# alarm.net
KiCad netlist of a schematic drawn in EasyEDA Pro
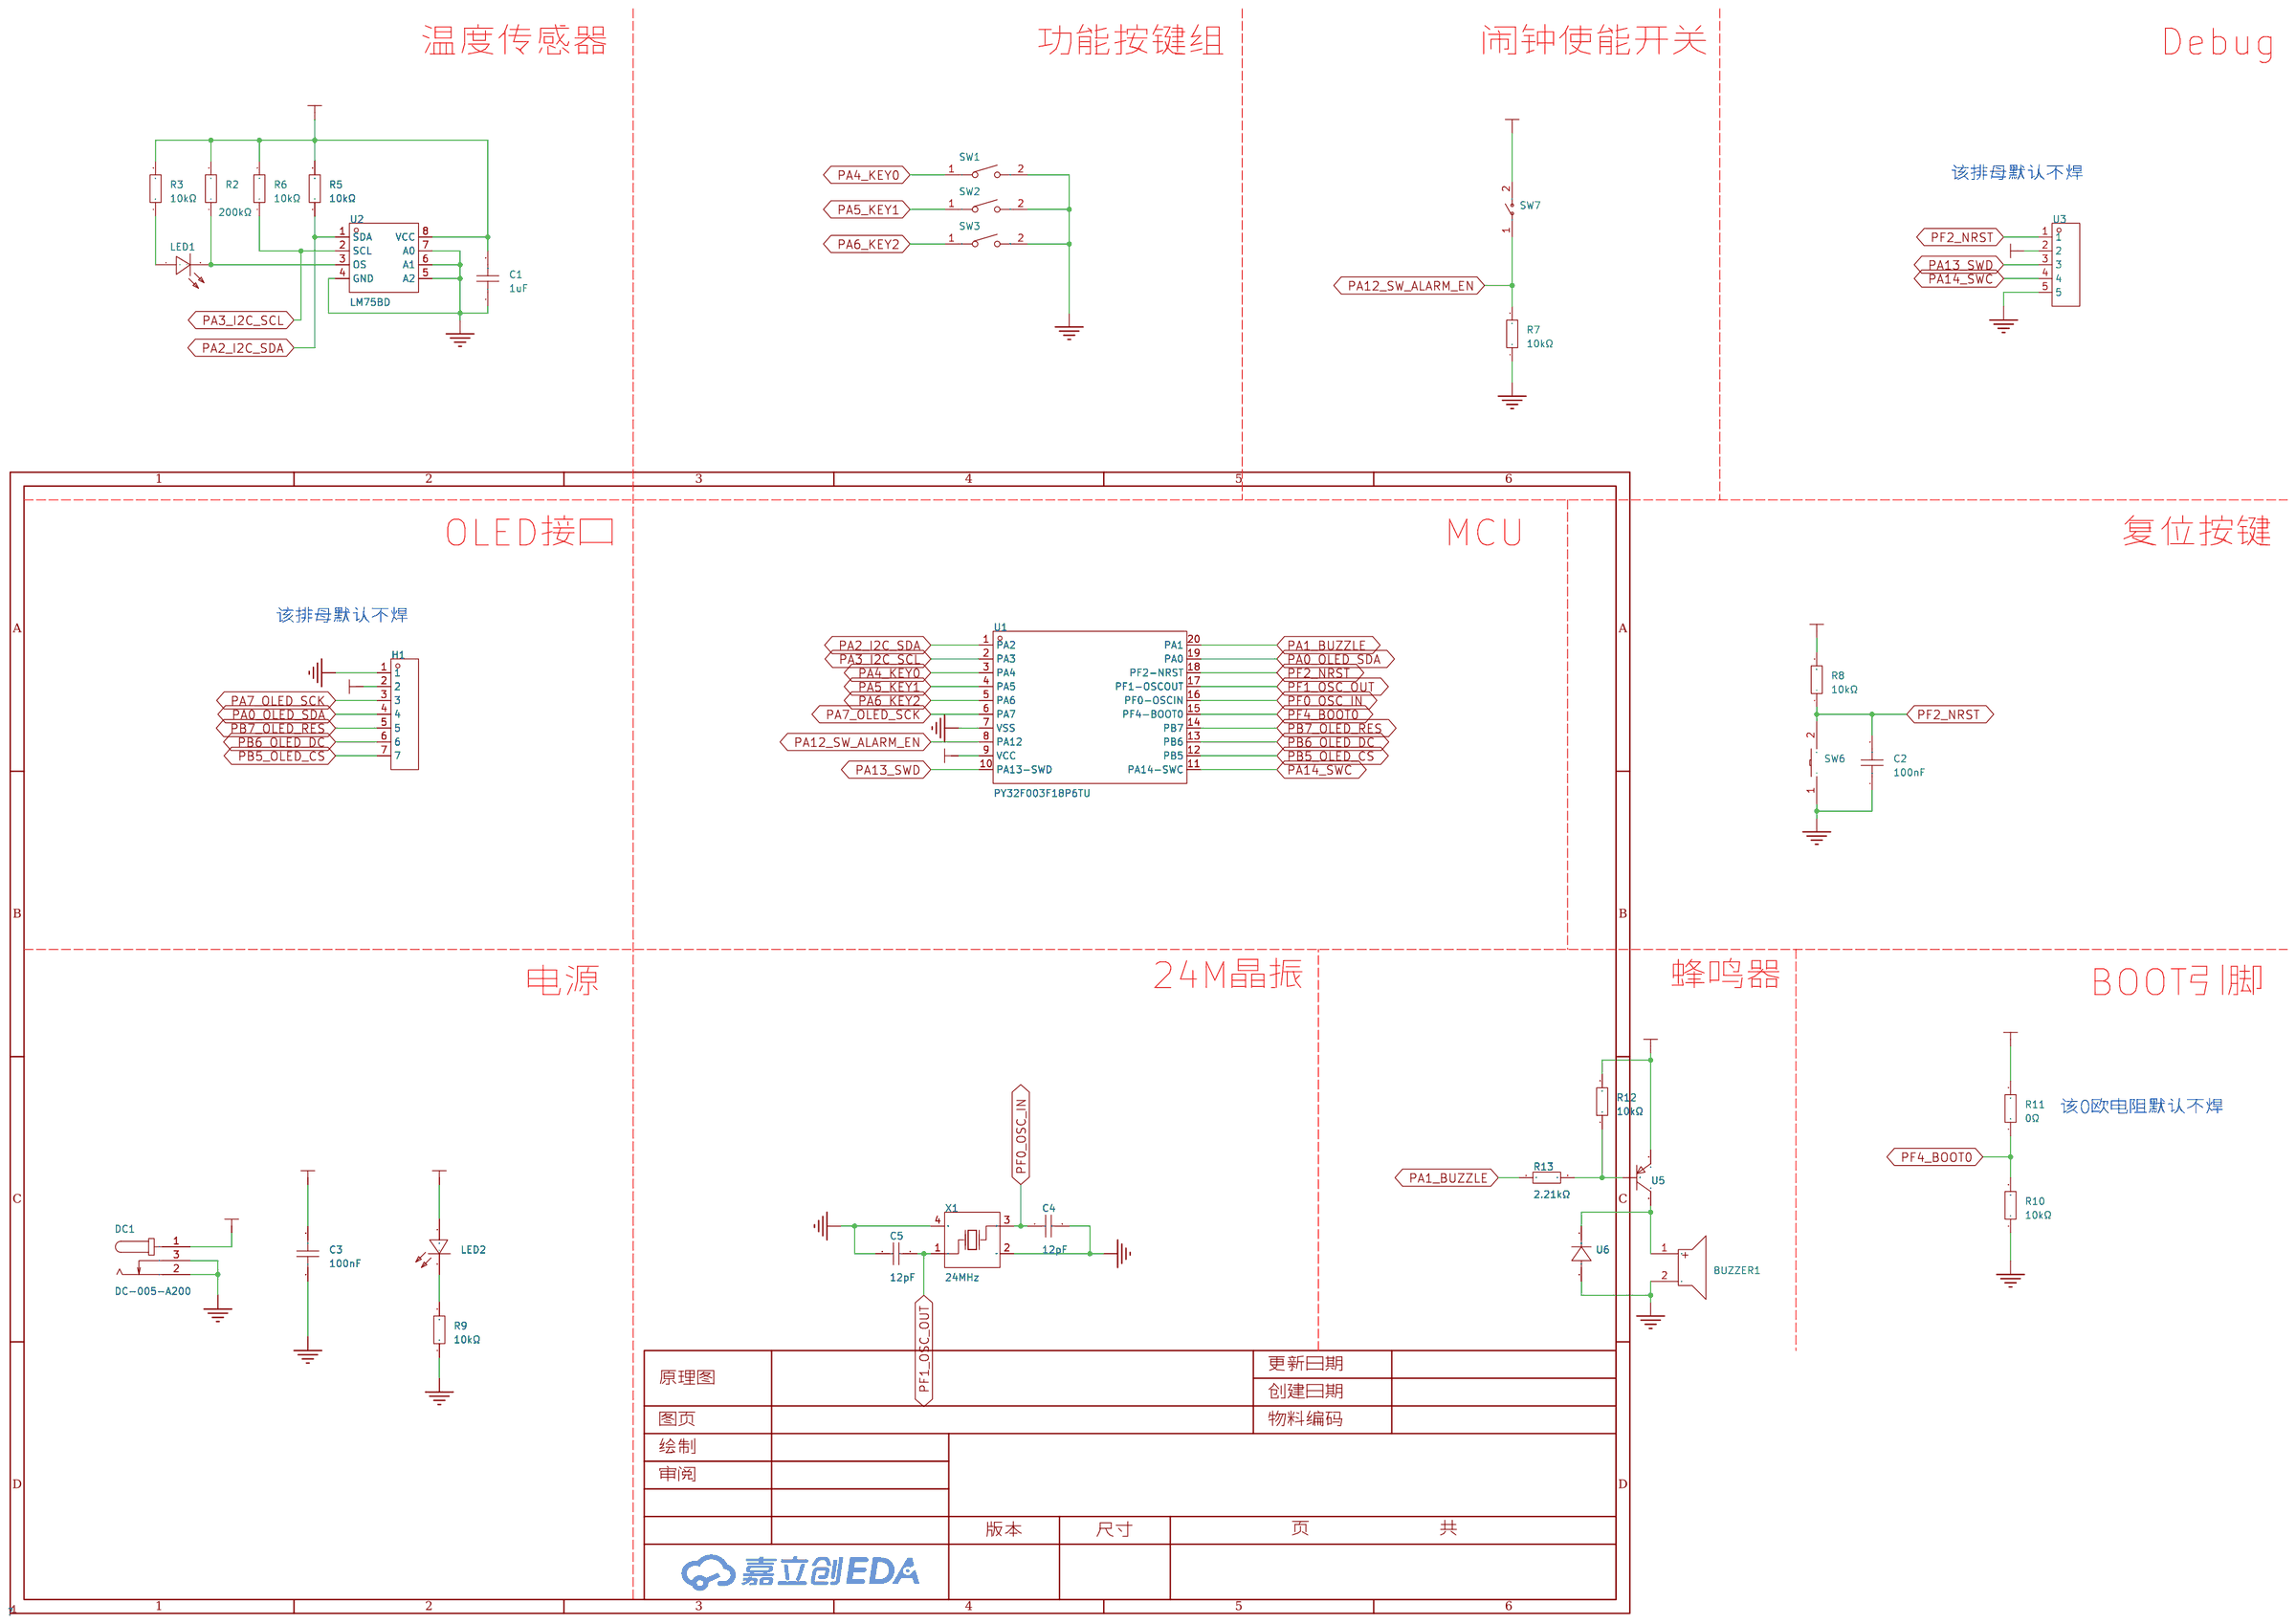
[diagram p0: schematic sheet]

(export (version "E")
  (design (tool "Eeschema 10.0.6"))
  (components
    (comp (ref "BUZZER1")
      (value "2.7kHz")
      (footprint "easyedapro:BUZ-TH_BD9.0-P4.00-D0.6-FD")
      (description "驱动方式:无源(外部驱动);构造类型:电磁式;频率:2.7kHz;声压(SPL):85dB@3V,10cm;")
      (fields (field (name "Manufacturer Part") "QMB-09B-03") (field (name "Manufacturer") "华能"))
      (libsource (lib "easyedapro") (part "QMB-09B-03"))
    )
    (comp (ref "C1")
      (value "1uF")
      (footprint "easyedapro:C0603")
      (description "容值:1uF;精度:±10%;额定电压:50V;材质(温度系数):X5R;")
      (fields
        (field (name "Manufacturer Part") "CL10A105KB8NNNC")
        (field (name "Manufacturer") "SAMSUNG(三星)")
      )
      (libsource (lib "easyedapro") (part "CL10A105KB8NNNC"))
    )
    (comp (ref "C2")
      (value "100nF")
      (footprint "easyedapro:C0603")
      (description "容值:100nF;精度:±10%;额定电压:50V;材质(温度系数):X7R;")
      (fields
        (field (name "Manufacturer Part") "CL10B104KB8NNNC")
        (field (name "Manufacturer") "SAMSUNG(三星)")
      )
      (libsource (lib "easyedapro") (part "CL10B104KB8NNNC"))
    )
    (comp (ref "C3")
      (value "100nF")
      (footprint "easyedapro:C0603")
      (description "容值:100nF;精度:±10%;额定电压:50V;材质(温度系数):X7R;")
      (fields
        (field (name "Manufacturer Part") "CL10B104KB8NNNC")
        (field (name "Manufacturer") "SAMSUNG(三星)")
      )
      (libsource (lib "easyedapro") (part "CL10B104KB8NNNC"))
    )
    (comp (ref "C4")
      (value "12pF")
      (footprint "easyedapro:C0603")
      (description "容值:12pF;精度:±5%;额定电压:50V;材质(温度系数):C0G;")
      (fields
        (field (name "Manufacturer Part") "CL10C120JB8NNNC")
        (field (name "Manufacturer") "SAMSUNG(三星)")
      )
      (libsource (lib "easyedapro") (part "CL10C120JB8NNNC"))
    )
    (comp (ref "C5")
      (value "12pF")
      (footprint "easyedapro:C0603")
      (description "容值:12pF;精度:±5%;额定电压:50V;材质(温度系数):C0G;")
      (fields
        (field (name "Manufacturer Part") "CL10C120JB8NNNC")
        (field (name "Manufacturer") "SAMSUNG(三星)")
      )
      (libsource (lib "easyedapro") (part "CL10C120JB8NNNC"))
    )
    (comp (ref "DC1")
      (value "DC-005-A200")
      (footprint "easyedapro:DC-IN-TH_DC-005-A200")
      (description "连接器类型:DC电源插座;安装方式:弯插;触点内径:2mm;触点外径:6.4mm;额定电流:3A;额定电压:30V;工作温度范围:-20°C~+70°C;")
      (fields (field (name "Manufacturer") "XUNPU(讯普)"))
      (libsource (lib "easyedapro") (part "DC-005-A200"))
    )
    (comp (ref "H1")
      (value "BX-PM2.54-1-7PY")
      (footprint "easyedapro:HDR-TH_7P-P2.54-V-F")
      (fields (field (name "Manufacturer") "Bossie(博锡)"))
      (libsource (lib "easyedapro") (part "BX-PM2.54-1-7PY"))
    )
    (comp (ref "LED1")
      (value "NCD0805R1")
      (footprint "easyedapro:LED0805-R-RD")
      (fields (field (name "Manufacturer") "国星光电"))
      (libsource (lib "easyedapro") (part "FC-2012HRK-620D"))
    )
    (comp (ref "LED2")
      (value "NCD0805R1")
      (footprint "easyedapro:LED0805-R-RD")
      (fields (field (name "Manufacturer") "国星光电"))
      (libsource (lib "easyedapro") (part "FC-2012HRK-620D"))
    )
    (comp (ref "R2")
      (value "200kΩ")
      (footprint "easyedapro:R0603")
      (description "电阻类型:厚膜电阻;阻值:200kΩ;精度:±1%;功率:100mW;最大工作电压:75V;温度系数:±100ppm/°C;")
      (fields
        (field (name "Manufacturer Part") "0603WAF2003T5E")
        (field (name "Manufacturer") "UNI-ROYAL(厚声)")
      )
      (libsource (lib "easyedapro") (part "0603WAF2003T5E"))
    )
    (comp (ref "R3")
      (value "10kΩ")
      (footprint "easyedapro:R0603")
      (description "电阻类型:厚膜电阻;阻值:10kΩ;精度:±1%;功率:100mW;最大工作电压:75V;温度系数:±100ppm/°C;")
      (fields
        (field (name "Manufacturer Part") "0603WAF1002T5E")
        (field (name "Manufacturer") "UNI-ROYAL(厚声)")
      )
      (libsource (lib "easyedapro") (part "0603WAF1002T5E"))
    )
    (comp (ref "R5")
      (value "10kΩ")
      (footprint "easyedapro:R0603")
      (description "电阻类型:厚膜电阻;阻值:10kΩ;精度:±1%;功率:100mW;最大工作电压:75V;温度系数:±100ppm/°C;")
      (fields
        (field (name "Manufacturer Part") "0603WAF1002T5E")
        (field (name "Manufacturer") "UNI-ROYAL(厚声)")
      )
      (libsource (lib "easyedapro") (part "0603WAF1002T5E"))
    )
    (comp (ref "R6")
      (value "10kΩ")
      (footprint "easyedapro:R0603")
      (description "电阻类型:厚膜电阻;阻值:10kΩ;精度:±1%;功率:100mW;最大工作电压:75V;温度系数:±100ppm/°C;")
      (fields
        (field (name "Manufacturer Part") "0603WAF1002T5E")
        (field (name "Manufacturer") "UNI-ROYAL(厚声)")
      )
      (libsource (lib "easyedapro") (part "0603WAF1002T5E"))
    )
    (comp (ref "R7")
      (value "10kΩ")
      (footprint "easyedapro:R0603")
      (description "电阻类型:厚膜电阻;阻值:10kΩ;精度:±1%;功率:100mW;最大工作电压:75V;温度系数:±100ppm/°C;")
      (fields
        (field (name "Manufacturer Part") "0603WAF1002T5E")
        (field (name "Manufacturer") "UNI-ROYAL(厚声)")
      )
      (libsource (lib "easyedapro") (part "0603WAF1002T5E"))
    )
    (comp (ref "R8")
      (value "10kΩ")
      (footprint "easyedapro:R0603")
      (description "电阻类型:厚膜电阻;阻值:10kΩ;精度:±1%;功率:100mW;最大工作电压:75V;温度系数:±100ppm/°C;")
      (fields
        (field (name "Manufacturer Part") "0603WAF1002T5E")
        (field (name "Manufacturer") "UNI-ROYAL(厚声)")
      )
      (libsource (lib "easyedapro") (part "0603WAF1002T5E"))
    )
    (comp (ref "R9")
      (value "10kΩ")
      (footprint "easyedapro:R0603")
      (description "电阻类型:厚膜电阻;阻值:10kΩ;精度:±1%;功率:100mW;最大工作电压:75V;温度系数:±100ppm/°C;")
      (fields
        (field (name "Manufacturer Part") "0603WAF1002T5E")
        (field (name "Manufacturer") "UNI-ROYAL(厚声)")
      )
      (libsource (lib "easyedapro") (part "0603WAF1002T5E"))
    )
    (comp (ref "R10")
      (value "10kΩ")
      (footprint "easyedapro:R0603")
      (description "电阻类型:厚膜电阻;阻值:10kΩ;精度:±1%;功率:100mW;最大工作电压:75V;温度系数:±100ppm/°C;")
      (fields
        (field (name "Manufacturer Part") "0603WAF1002T5E")
        (field (name "Manufacturer") "UNI-ROYAL(厚声)")
      )
      (libsource (lib "easyedapro") (part "0603WAF1002T5E"))
    )
    (comp (ref "R11")
      (value "0Ω")
      (footprint "easyedapro:R0805")
      (description "电阻类型:厚膜电阻;阻值:0Ω;精度:±1%;功率:125mW;最大工作电压:150V;温度系数:±800ppm/°C;")
      (fields
        (field (name "Manufacturer Part") "0805W8F0000T5E")
        (field (name "Manufacturer") "UNI-ROYAL(厚声)")
      )
      (libsource (lib "easyedapro") (part "0805W8F0000T5E"))
    )
    (comp (ref "R12")
      (value "10kΩ")
      (footprint "easyedapro:R0603")
      (description "电阻类型:厚膜电阻;阻值:10kΩ;精度:±1%;功率:100mW;最大工作电压:75V;温度系数:±100ppm/°C;")
      (fields
        (field (name "Manufacturer Part") "0603WAF1002T5E")
        (field (name "Manufacturer") "UNI-ROYAL(厚声)")
      )
      (libsource (lib "easyedapro") (part "0603WAF1002T5E"))
    )
    (comp (ref "R13")
      (value "2.21kΩ")
      (footprint "easyedapro:R0603")
      (description "电阻类型:厚膜电阻;阻值:2.21kΩ;精度:±1%;功率:100mW;最大工作电压:75V;温度系数:±100ppm/°C;")
      (fields
        (field (name "Manufacturer Part") "0603WAF2211T5E")
        (field (name "Manufacturer") "UNI-ROYAL(厚声)")
      )
      (libsource (lib "easyedapro") (part "0603WAF2211T5E"))
    )
    (comp (ref "SW1")
      (value "TS-1088-AR02016")
      (footprint "easyedapro:SW-SMD_L3.9-W3.0-P4.45")
      (fields (field (name "Manufacturer") "XUNPU(讯普)"))
      (libsource (lib "easyedapro") (part "TS-1088-AR02016"))
    )
    (comp (ref "SW2")
      (value "TS-1088-AR02016")
      (footprint "easyedapro:SW-SMD_L3.9-W3.0-P4.45")
      (fields (field (name "Manufacturer") "XUNPU(讯普)"))
      (libsource (lib "easyedapro") (part "TS-1088-AR02016"))
    )
    (comp (ref "SW3")
      (value "TS-1088-AR02016")
      (footprint "easyedapro:SW-SMD_L3.9-W3.0-P4.45")
      (fields (field (name "Manufacturer") "XUNPU(讯普)"))
      (libsource (lib "easyedapro") (part "TS-1088-AR02016"))
    )
    (comp (ref "SW6")
      (value "TS-1101-C-W")
      (footprint "easyedapro:SW-SMD_L6.0-W3.3-LS8.0")
      (fields (field (name "Manufacturer") "XKB Connectivity(中国星坤)"))
      (libsource (lib "easyedapro") (part "TS-1101-C-W"))
    )
    (comp (ref "SW7")
      (value "KCD11-2P-R")
      (footprint "easyedapro:SW-TH_2P-L15.0-W10.5-P5.00_KCD11-2P-R")
      (description "带灯:无;引脚样式:焊片;额定电流:3A;额定电压(AC):250V;额定电压(DC):-;电路结构:单刀单掷;机械寿命:1万次;")
      (fields (field (name "Manufacturer") "SHOU HAN(首韩)"))
      (libsource (lib "easyedapro") (part "KCD11-2P-R"))
    )
    (comp (ref "U1")
      (value "PY32F003F18P6TU")
      (footprint "easyedapro:TSSOP-20_L6.5-W4.4-P0.65-LS6.4-BL")
      (fields (field (name "Manufacturer") "PUYA(普冉)"))
      (libsource (lib "easyedapro") (part "PY32F003F18P6TU"))
    )
    (comp (ref "U2")
      (value "LM75BD")
      (footprint "easyedapro:SOIC-8_L4.9-W3.9-P1.27-LS6.0-BL")
      (description "温度范围:-55°C~+125°C;精度:±3°C;接口类型:I2C;")
      (fields (field (name "Manufacturer") "UMW(友台半导体)"))
      (libsource (lib "easyedapro") (part "LM75BD"))
    )
    (comp (ref "U3")
      (value "BX-PM2.54-1-5PY")
      (footprint "easyedapro:HDR-TH_5P-P2.54-V-F-B")
      (fields (field (name "Manufacturer") "Bossie(博锡)"))
      (libsource (lib "easyedapro") (part "BX-PM2.54-1-5PY"))
    )
    (comp (ref "U5")
      (value "MMBT3906")
      (footprint "easyedapro:SOT-23-3_L2.9-W1.3-P1.90-LS2.4-BR")
      (description "晶体管类型:PNP;集电极电流(Ic):200mA;集射极击穿电压(Vceo):40V;功率(Pd):300mW;直流电流增益(hFE@Ic,Vce):100@10mA,1.0V;")
      (fields (field (name "Manufacturer") "宏迦橙"))
      (libsource (lib "easyedapro") (part "MMBT3906_C7420354"))
    )
    (comp (ref "U6")
      (value "1N4007W")
      (footprint "easyedapro:SOD-123FL_L2.7-W1.8-LS3.7-RD")
      (description "二极管配置:独立式;正向压降(Vf):1.1V@1A;直流反向耐压(Vr):1kV;整流电流:1A;")
      (fields (field (name "Manufacturer") "MSKSEMI(美森科)"))
      (libsource (lib "easyedapro") (part "1N4007W_C7528871"))
    )
    (comp (ref "X1")
      (value "24MHz")
      (footprint "easyedapro:CRYSTAL-SMD_4P-L3.2-W2.5-BL")
      (description "晶振类型:贴片晶振;频率:24MHz;常温频差:±10ppm;外接负载电容:12pF;频率稳定度(全温):±20ppm;")
      (fields (field (name "Manufacturer Part") "X322524MOB4SI") (field (name "Manufacturer") "YXC(扬兴晶振)"))
      (libsource (lib "easyedapro") (part "X322524MOB4SI"))
    )
  )
  (nets
    (net (code "1") (name "3V3") (class "Default")
      (node (ref "C1") (pin "2") (pinfunction "2_2") (pintype "unspecified"))
      (node (ref "C3") (pin "2") (pinfunction "2_2") (pintype "unspecified"))
      (node (ref "DC1") (pin "1") (pinfunction "1_1") (pintype "unspecified"))
      (node (ref "H1") (pin "2") (pinfunction "2_2") (pintype "unspecified"))
      (node (ref "LED2") (pin "1") (pinfunction "+_1") (pintype "unspecified"))
      (node (ref "R11") (pin "2") (pinfunction "2_2") (pintype "input"))
      (node (ref "R12") (pin "2") (pinfunction "2_2") (pintype "input"))
      (node (ref "R2") (pin "2") (pinfunction "2_2") (pintype "input"))
      (node (ref "R3") (pin "2") (pinfunction "2_2") (pintype "input"))
      (node (ref "R5") (pin "2") (pinfunction "2_2") (pintype "input"))
      (node (ref "R6") (pin "2") (pinfunction "2_2") (pintype "input"))
      (node (ref "R8") (pin "2") (pinfunction "2_2") (pintype "input"))
      (node (ref "SW7") (pin "2") (pinfunction "2_2") (pintype "unspecified"))
      (node (ref "U1") (pin "9") (pinfunction "VCC_9") (pintype "unspecified"))
      (node (ref "U2") (pin "8") (pinfunction "VCC_8") (pintype "unspecified"))
      (node (ref "U3") (pin "2") (pinfunction "2_2") (pintype "unspecified"))
      (node (ref "U5") (pin "2") (pinfunction "E_2") (pintype "input"))
    )
    (net (code "2") (name "GND") (class "Default")
      (node (ref "BUZZER1") (pin "2") (pinfunction "2_2") (pintype "unspecified"))
      (node (ref "C1") (pin "1") (pinfunction "1_1") (pintype "unspecified"))
      (node (ref "C2") (pin "1") (pinfunction "1_1") (pintype "unspecified"))
      (node (ref "C3") (pin "1") (pinfunction "1_1") (pintype "unspecified"))
      (node (ref "C4") (pin "2") (pinfunction "2_2") (pintype "input"))
      (node (ref "C5") (pin "1") (pinfunction "1_1") (pintype "input"))
      (node (ref "DC1") (pin "2") (pinfunction "2_2") (pintype "unspecified"))
      (node (ref "DC1") (pin "3") (pinfunction "3_3") (pintype "unspecified"))
      (node (ref "H1") (pin "1") (pinfunction "1_1") (pintype "unspecified"))
      (node (ref "R10") (pin "1") (pinfunction "1_1") (pintype "input"))
      (node (ref "R7") (pin "1") (pinfunction "1_1") (pintype "input"))
      (node (ref "R9") (pin "1") (pinfunction "1_1") (pintype "input"))
      (node (ref "SW1") (pin "2") (pinfunction "2_2") (pintype "unspecified"))
      (node (ref "SW2") (pin "2") (pinfunction "2_2") (pintype "unspecified"))
      (node (ref "SW3") (pin "2") (pinfunction "2_2") (pintype "unspecified"))
      (node (ref "SW6") (pin "1") (pinfunction "1_1") (pintype "unspecified"))
      (node (ref "U1") (pin "7") (pinfunction "VSS_7") (pintype "unspecified"))
      (node (ref "U2") (pin "4") (pinfunction "GND_4") (pintype "unspecified"))
      (node (ref "U2") (pin "5") (pinfunction "A2_5") (pintype "unspecified"))
      (node (ref "U2") (pin "6") (pinfunction "A1_6") (pintype "unspecified"))
      (node (ref "U2") (pin "7") (pinfunction "A0_7") (pintype "unspecified"))
      (node (ref "U3") (pin "5") (pinfunction "5_5") (pintype "unspecified"))
      (node (ref "U6") (pin "2") (pinfunction "A_2") (pintype "unspecified"))
      (node (ref "X1") (pin "2") (pinfunction "GND_2") (pintype "unspecified"))
      (node (ref "X1") (pin "4") (pinfunction "GND_4") (pintype "unspecified"))
    )
    (net (code "3") (name "Net-(LED1-+)") (class "Default")
      (node (ref "LED1") (pin "1") (pinfunction "+_1") (pintype "unspecified"))
      (node (ref "R3") (pin "1") (pinfunction "1_1") (pintype "input"))
    )
    (net (code "4") (name "Net-(LED1--)") (class "Default")
      (node (ref "LED1") (pin "2") (pinfunction "-_2") (pintype "unspecified"))
      (node (ref "R2") (pin "1") (pinfunction "1_1") (pintype "input"))
      (node (ref "U2") (pin "3") (pinfunction "OS_3") (pintype "unspecified"))
    )
    (net (code "5") (name "Net-(LED2--)") (class "Default")
      (node (ref "LED2") (pin "2") (pinfunction "-_2") (pintype "unspecified"))
      (node (ref "R9") (pin "2") (pinfunction "2_2") (pintype "input"))
    )
    (net (code "6") (name "Net-(U5-B)") (class "Default")
      (node (ref "R12") (pin "1") (pinfunction "1_1") (pintype "input"))
      (node (ref "R13") (pin "2") (pinfunction "2_2") (pintype "input"))
      (node (ref "U5") (pin "1") (pinfunction "B_1") (pintype "input"))
    )
    (net (code "7") (name "Net-(U5-C)") (class "Default")
      (node (ref "BUZZER1") (pin "1") (pinfunction "1_1") (pintype "unspecified"))
      (node (ref "U5") (pin "3") (pinfunction "C_3") (pintype "input"))
      (node (ref "U6") (pin "1") (pinfunction "K_1") (pintype "unspecified"))
    )
    (net (code "8") (name "PA0_OLED_SDA") (class "Default")
      (node (ref "H1") (pin "4") (pinfunction "4_4") (pintype "unspecified"))
      (node (ref "U1") (pin "19") (pinfunction "PA0_19") (pintype "unspecified"))
    )
    (net (code "9") (name "PA1_BUZZLE") (class "Default")
      (node (ref "R13") (pin "1") (pinfunction "1_1") (pintype "input"))
      (node (ref "U1") (pin "20") (pinfunction "PA1_20") (pintype "unspecified"))
    )
    (net (code "10") (name "PA2_I2C_SDA") (class "Default")
      (node (ref "R5") (pin "1") (pinfunction "1_1") (pintype "input"))
      (node (ref "U1") (pin "1") (pinfunction "PA2_1") (pintype "unspecified"))
      (node (ref "U2") (pin "1") (pinfunction "SDA_1") (pintype "unspecified"))
    )
    (net (code "11") (name "PA3_I2C_SCL") (class "Default")
      (node (ref "R6") (pin "1") (pinfunction "1_1") (pintype "input"))
      (node (ref "U1") (pin "2") (pinfunction "PA3_2") (pintype "unspecified"))
      (node (ref "U2") (pin "2") (pinfunction "SCL_2") (pintype "unspecified"))
    )
    (net (code "12") (name "PA4_KEY0") (class "Default")
      (node (ref "SW1") (pin "1") (pinfunction "1_1") (pintype "unspecified"))
      (node (ref "U1") (pin "3") (pinfunction "PA4_3") (pintype "unspecified"))
    )
    (net (code "13") (name "PA5_KEY1") (class "Default")
      (node (ref "SW2") (pin "1") (pinfunction "1_1") (pintype "unspecified"))
      (node (ref "U1") (pin "4") (pinfunction "PA5_4") (pintype "unspecified"))
    )
    (net (code "14") (name "PA6_KEY2") (class "Default")
      (node (ref "SW3") (pin "1") (pinfunction "1_1") (pintype "unspecified"))
      (node (ref "U1") (pin "5") (pinfunction "PA6_5") (pintype "unspecified"))
    )
    (net (code "15") (name "PA7_OLED_SCK") (class "Default")
      (node (ref "H1") (pin "3") (pinfunction "3_3") (pintype "unspecified"))
      (node (ref "U1") (pin "6") (pinfunction "PA7_6") (pintype "unspecified"))
    )
    (net (code "16") (name "PA12_SW_ALARM_EN") (class "Default")
      (node (ref "R7") (pin "2") (pinfunction "2_2") (pintype "input"))
      (node (ref "SW7") (pin "1") (pinfunction "1_1") (pintype "unspecified"))
      (node (ref "U1") (pin "8") (pinfunction "PA12_8") (pintype "unspecified"))
    )
    (net (code "17") (name "PA13_SWD") (class "Default")
      (node (ref "U1") (pin "10") (pinfunction "PA13-SWD_10") (pintype "unspecified"))
      (node (ref "U3") (pin "3") (pinfunction "3_3") (pintype "unspecified"))
    )
    (net (code "18") (name "PA14_SWC") (class "Default")
      (node (ref "U1") (pin "11") (pinfunction "PA14-SWC_11") (pintype "unspecified"))
      (node (ref "U3") (pin "4") (pinfunction "4_4") (pintype "unspecified"))
    )
    (net (code "19") (name "PB5_OLED_CS") (class "Default")
      (node (ref "H1") (pin "7") (pinfunction "7_7") (pintype "unspecified"))
      (node (ref "U1") (pin "12") (pinfunction "PB5_12") (pintype "unspecified"))
    )
    (net (code "20") (name "PB6_OLED_DC") (class "Default")
      (node (ref "H1") (pin "6") (pinfunction "6_6") (pintype "unspecified"))
      (node (ref "U1") (pin "13") (pinfunction "PB6_13") (pintype "unspecified"))
    )
    (net (code "21") (name "PB7_OLED_RES") (class "Default")
      (node (ref "H1") (pin "5") (pinfunction "5_5") (pintype "unspecified"))
      (node (ref "U1") (pin "14") (pinfunction "PB7_14") (pintype "unspecified"))
    )
    (net (code "22") (name "PF0_OSC_IN") (class "Default")
      (node (ref "C4") (pin "1") (pinfunction "1_1") (pintype "input"))
      (node (ref "U1") (pin "16") (pinfunction "PF0-OSCIN_16") (pintype "unspecified"))
      (node (ref "X1") (pin "3") (pinfunction "OSC2_3") (pintype "unspecified"))
    )
    (net (code "23") (name "PF1_OSC_OUT") (class "Default")
      (node (ref "C5") (pin "2") (pinfunction "2_2") (pintype "input"))
      (node (ref "U1") (pin "17") (pinfunction "PF1-OSCOUT_17") (pintype "unspecified"))
      (node (ref "X1") (pin "1") (pinfunction "OSC1_1") (pintype "unspecified"))
    )
    (net (code "24") (name "PF2_NRST") (class "Default")
      (node (ref "C2") (pin "2") (pinfunction "2_2") (pintype "unspecified"))
      (node (ref "R8") (pin "1") (pinfunction "1_1") (pintype "input"))
      (node (ref "SW6") (pin "2") (pinfunction "2_2") (pintype "unspecified"))
      (node (ref "U1") (pin "18") (pinfunction "PF2-NRST_18") (pintype "unspecified"))
      (node (ref "U3") (pin "1") (pinfunction "1_1") (pintype "unspecified"))
    )
    (net (code "25") (name "PF4_BOOT0") (class "Default")
      (node (ref "R10") (pin "2") (pinfunction "2_2") (pintype "input"))
      (node (ref "R11") (pin "1") (pinfunction "1_1") (pintype "input"))
      (node (ref "U1") (pin "15") (pinfunction "PF4-BOOT0_15") (pintype "unspecified"))
    )
  )
)
